# MXChip-EMW3166-v1_0_0.net
KiCad netlist of a schematic drawn in EAGLE
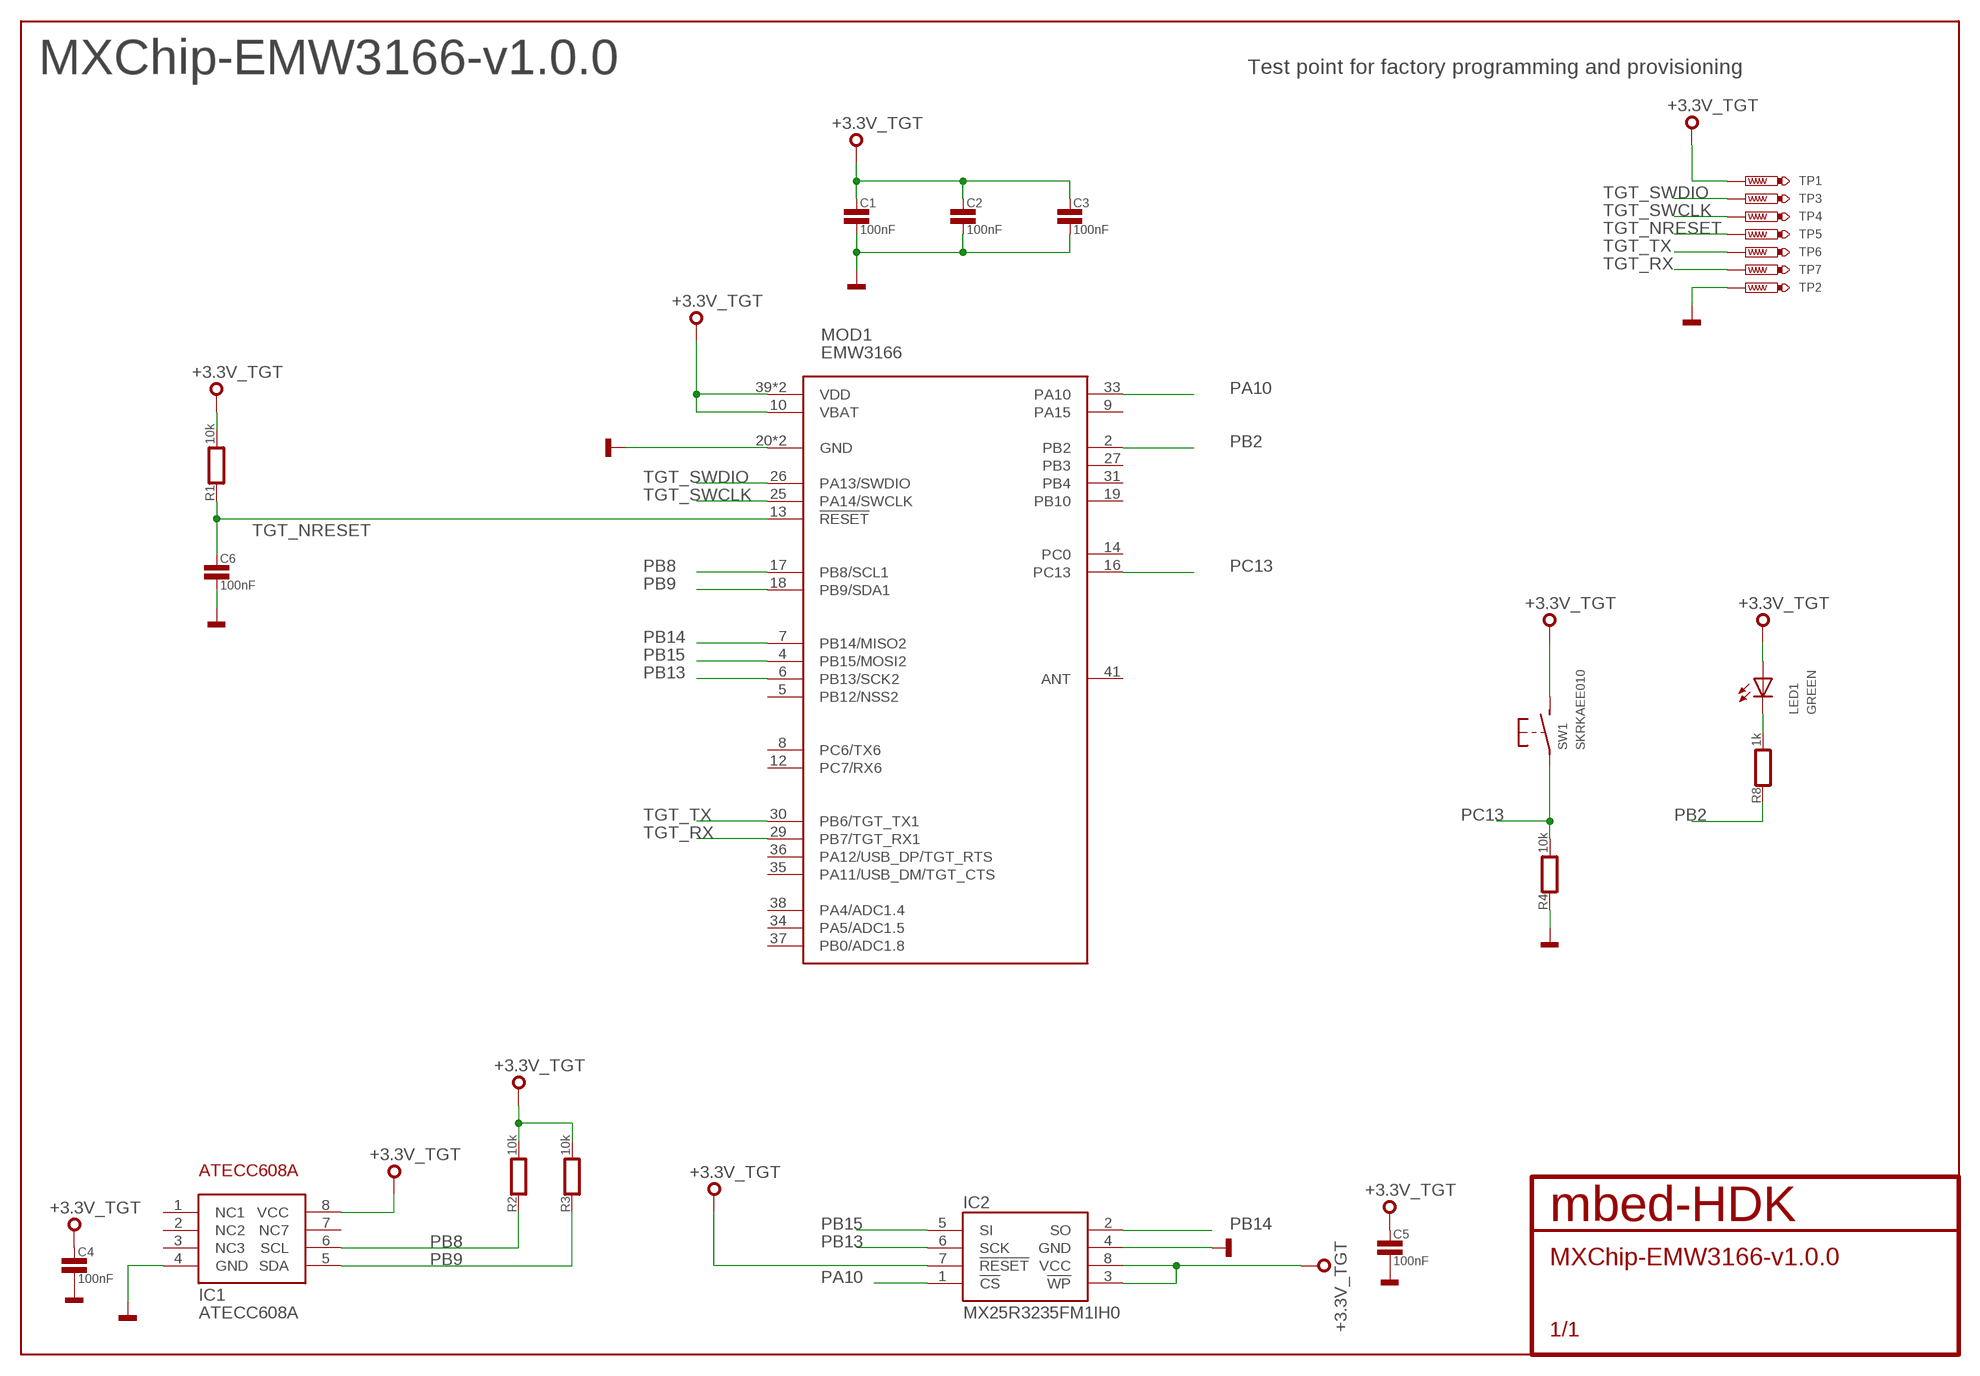
[diagram p0: schematic, sheet 1]

(export (version "E")
  (design (tool "Eeschema 10.0.6"))
  (components
    (comp (ref "C1")
      (value "100nF")
      (footprint "eagle-import:0603")
      (libsource (lib "eagle-import") (part "C0603"))
    )
    (comp (ref "C2")
      (value "100nF")
      (footprint "eagle-import:0603")
      (libsource (lib "eagle-import") (part "C0603"))
    )
    (comp (ref "C3")
      (value "100nF")
      (footprint "eagle-import:0603")
      (libsource (lib "eagle-import") (part "C0603"))
    )
    (comp (ref "C4")
      (value "100nF")
      (footprint "eagle-import:0603")
      (libsource (lib "eagle-import") (part "C0603"))
    )
    (comp (ref "C5")
      (value "100nF")
      (footprint "eagle-import:0603")
      (libsource (lib "eagle-import") (part "C0603"))
    )
    (comp (ref "C6")
      (value "100nF")
      (footprint "eagle-import:0603")
      (libsource (lib "eagle-import") (part "C0603"))
    )
    (comp (ref "IC1")
      (value "ATECC608A")
      (footprint "eagle-import:SO8")
      (fields (field (name "MF") "Atmel"))
      (libsource (lib "eagle-import") (part "ATECC608A"))
    )
    (comp (ref "IC2")
      (value "MX25R3235FM1IH0")
      (footprint "eagle-import:SO8")
      (fields (field (name "MF") "Macronix"))
      (libsource (lib "eagle-import") (part "MX25R3235FM1IH0"))
    )
    (comp (ref "LED1")
      (value "GREEN")
      (footprint "eagle-import:CHIPLED_0603")
      (fields (field (name "MF") "Wurth Electronics Inc"))
      (libsource (lib "eagle-import") (part "SMD_LED0603"))
    )
    (comp (ref "MOD1")
      (value "EMW3166")
      (footprint "eagle-import:EMW3166")
      (libsource (lib "eagle-import") (part "EMW3166"))
    )
    (comp (ref "R1")
      (value "10k")
      (footprint "eagle-import:0603")
      (libsource (lib "eagle-import") (part "R0603"))
    )
    (comp (ref "R2")
      (value "10k")
      (footprint "eagle-import:0603")
      (libsource (lib "eagle-import") (part "R0603"))
    )
    (comp (ref "R3")
      (value "10k")
      (footprint "eagle-import:0603")
      (libsource (lib "eagle-import") (part "R0603"))
    )
    (comp (ref "R4")
      (value "10k")
      (footprint "eagle-import:0603")
      (libsource (lib "eagle-import") (part "R0603"))
    )
    (comp (ref "R8")
      (value "1k")
      (footprint "eagle-import:0603")
      (libsource (lib "eagle-import") (part "R0603"))
    )
    (comp (ref "SW1")
      (value "SKRKAEE010")
      (footprint "eagle-import:SKRKAEE010")
      (fields (field (name "MF") "ALPS"))
      (libsource (lib "eagle-import") (part "SKRKAEE010"))
    )
    (comp (ref "TP1")
      (value "TEST_POINT-50R-SMD")
      (footprint "eagle-import:TP50-SMD")
      (libsource (lib "eagle-import") (part "TEST_POINT-50R-SMD"))
    )
    (comp (ref "TP2")
      (value "TEST_POINT-50R-SMD")
      (footprint "eagle-import:TP50-SMD")
      (libsource (lib "eagle-import") (part "TEST_POINT-50R-SMD"))
    )
    (comp (ref "TP3")
      (value "TEST_POINT-50R-SMD")
      (footprint "eagle-import:TP50-SMD")
      (libsource (lib "eagle-import") (part "TEST_POINT-50R-SMD"))
    )
    (comp (ref "TP4")
      (value "TEST_POINT-50R-SMD")
      (footprint "eagle-import:TP50-SMD")
      (libsource (lib "eagle-import") (part "TEST_POINT-50R-SMD"))
    )
    (comp (ref "TP5")
      (value "TEST_POINT-50R-SMD")
      (footprint "eagle-import:TP50-SMD")
      (libsource (lib "eagle-import") (part "TEST_POINT-50R-SMD"))
    )
    (comp (ref "TP6")
      (value "TEST_POINT-50R-SMD")
      (footprint "eagle-import:TP50-SMD")
      (libsource (lib "eagle-import") (part "TEST_POINT-50R-SMD"))
    )
    (comp (ref "TP7")
      (value "TEST_POINT-50R-SMD")
      (footprint "eagle-import:TP50-SMD")
      (libsource (lib "eagle-import") (part "TEST_POINT-50R-SMD"))
    )
  )
  (nets
    (net (code "1") (name "+3.3V_TGT") (class "Default")
      (node (ref "C1") (pin "1") (pinfunction "P$1_1") (pintype "passive"))
      (node (ref "C2") (pin "1") (pinfunction "P$1_1") (pintype "passive"))
      (node (ref "C3") (pin "1") (pinfunction "P$1_1") (pintype "passive"))
      (node (ref "C4") (pin "1") (pinfunction "P$1_1") (pintype "passive"))
      (node (ref "C5") (pin "1") (pinfunction "P$1_1") (pintype "passive"))
      (node (ref "IC1") (pin "8") (pinfunction "VCC_8") (pintype "bidirectional"))
      (node (ref "IC2") (pin "3") (pinfunction "~{WP}_3") (pintype "bidirectional"))
      (node (ref "IC2") (pin "7") (pinfunction "~{RESET}_7") (pintype "bidirectional"))
      (node (ref "IC2") (pin "8") (pinfunction "VCC_8") (pintype "bidirectional"))
      (node (ref "LED1") (pin "A") (pinfunction "A_A") (pintype "passive"))
      (node (ref "MOD1") (pin "10") (pinfunction "VBAT_10") (pintype "bidirectional"))
      (node (ref "MOD1") (pin "39") (pinfunction "VDD_39") (pintype "bidirectional"))
      (node (ref "MOD1") (pin "40") (pinfunction "VDD_40") (pintype "bidirectional"))
      (node (ref "R1") (pin "2") (pinfunction "P$2_2") (pintype "passive"))
      (node (ref "R2") (pin "2") (pinfunction "P$2_2") (pintype "passive"))
      (node (ref "R3") (pin "2") (pinfunction "P$2_2") (pintype "passive"))
      (node (ref "SW1") (pin "P$2") (pinfunction "S_P$2") (pintype "passive"))
      (node (ref "TP1") (pin "TP") (pinfunction "TP_TP") (pintype "input"))
    )
    (net (code "2") (name "/PA10") (class "Default")
      (node (ref "IC2") (pin "1") (pinfunction "~{CS}_1") (pintype "bidirectional"))
      (node (ref "MOD1") (pin "33") (pinfunction "PA10_33") (pintype "bidirectional"))
    )
    (net (code "3") (name "/PB2") (class "Default")
      (node (ref "MOD1") (pin "2") (pinfunction "PB2_2") (pintype "bidirectional"))
      (node (ref "R8") (pin "1") (pinfunction "P$1_1") (pintype "passive"))
    )
    (net (code "4") (name "/PB8") (class "Default")
      (node (ref "IC1") (pin "6") (pinfunction "SCL_6") (pintype "bidirectional"))
      (node (ref "MOD1") (pin "17") (pinfunction "PB8/SCL1_17") (pintype "bidirectional"))
      (node (ref "R2") (pin "1") (pinfunction "P$1_1") (pintype "passive"))
    )
    (net (code "5") (name "/PB9") (class "Default")
      (node (ref "IC1") (pin "5") (pinfunction "SDA_5") (pintype "bidirectional"))
      (node (ref "MOD1") (pin "18") (pinfunction "PB9/SDA1_18") (pintype "bidirectional"))
      (node (ref "R3") (pin "1") (pinfunction "P$1_1") (pintype "passive"))
    )
    (net (code "6") (name "/PB13") (class "Default")
      (node (ref "IC2") (pin "6") (pinfunction "SCK_6") (pintype "bidirectional"))
      (node (ref "MOD1") (pin "6") (pinfunction "PB13/SCK2_6") (pintype "bidirectional"))
    )
    (net (code "7") (name "/PB14") (class "Default")
      (node (ref "IC2") (pin "2") (pinfunction "SO_2") (pintype "bidirectional"))
      (node (ref "MOD1") (pin "7") (pinfunction "PB14/MISO2_7") (pintype "bidirectional"))
    )
    (net (code "8") (name "/PB15") (class "Default")
      (node (ref "IC2") (pin "5") (pinfunction "SI_5") (pintype "bidirectional"))
      (node (ref "MOD1") (pin "4") (pinfunction "PB15/MOSI2_4") (pintype "bidirectional"))
    )
    (net (code "9") (name "/PC13") (class "Default")
      (node (ref "MOD1") (pin "16") (pinfunction "PC13_16") (pintype "bidirectional"))
      (node (ref "R4") (pin "2") (pinfunction "P$2_2") (pintype "passive"))
      (node (ref "SW1") (pin "P$1") (pinfunction "P_P$1") (pintype "passive"))
    )
    (net (code "10") (name "/TGT_NRESET") (class "Default")
      (node (ref "C6") (pin "1") (pinfunction "P$1_1") (pintype "passive"))
      (node (ref "MOD1") (pin "13") (pinfunction "~{RESET}_13") (pintype "bidirectional"))
      (node (ref "R1") (pin "1") (pinfunction "P$1_1") (pintype "passive"))
      (node (ref "TP5") (pin "TP") (pinfunction "TP_TP") (pintype "input"))
    )
    (net (code "11") (name "/TGT_RX") (class "Default")
      (node (ref "MOD1") (pin "29") (pinfunction "PB7/TGT_RX1_29") (pintype "bidirectional"))
      (node (ref "TP7") (pin "TP") (pinfunction "TP_TP") (pintype "input"))
    )
    (net (code "12") (name "/TGT_SWCLK") (class "Default")
      (node (ref "MOD1") (pin "25") (pinfunction "PA14/SWCLK_25") (pintype "bidirectional"))
      (node (ref "TP4") (pin "TP") (pinfunction "TP_TP") (pintype "input"))
    )
    (net (code "13") (name "/TGT_SWDIO") (class "Default")
      (node (ref "MOD1") (pin "26") (pinfunction "PA13/SWDIO_26") (pintype "bidirectional"))
      (node (ref "TP3") (pin "TP") (pinfunction "TP_TP") (pintype "input"))
    )
    (net (code "14") (name "/TGT_TX") (class "Default")
      (node (ref "MOD1") (pin "30") (pinfunction "PB6/TGT_TX1_30") (pintype "bidirectional"))
      (node (ref "TP6") (pin "TP") (pinfunction "TP_TP") (pintype "input"))
    )
    (net (code "15") (name "GND") (class "Default")
      (node (ref "C1") (pin "2") (pinfunction "P$2_2") (pintype "passive"))
      (node (ref "C2") (pin "2") (pinfunction "P$2_2") (pintype "passive"))
      (node (ref "C3") (pin "2") (pinfunction "P$2_2") (pintype "passive"))
      (node (ref "C4") (pin "2") (pinfunction "P$2_2") (pintype "passive"))
      (node (ref "C5") (pin "2") (pinfunction "P$2_2") (pintype "passive"))
      (node (ref "C6") (pin "2") (pinfunction "P$2_2") (pintype "passive"))
      (node (ref "IC1") (pin "4") (pinfunction "GND_4") (pintype "bidirectional"))
      (node (ref "IC2") (pin "4") (pinfunction "GND_4") (pintype "bidirectional"))
      (node (ref "MOD1") (pin "20") (pinfunction "GND_20") (pintype "bidirectional"))
      (node (ref "MOD1") (pin "21") (pinfunction "GND_21") (pintype "bidirectional"))
      (node (ref "R4") (pin "1") (pinfunction "P$1_1") (pintype "passive"))
      (node (ref "TP2") (pin "TP") (pinfunction "TP_TP") (pintype "input"))
    )
    (net (code "16") (name "Net-(R8-P$2)") (class "Default")
      (node (ref "LED1") (pin "C") (pinfunction "C_C") (pintype "passive"))
      (node (ref "R8") (pin "2") (pinfunction "P$2_2") (pintype "passive"))
    )
    (net (code "17") (name "unconnected-(IC1-NC1-Pad1)") (class "Default")
      (node (ref "IC1") (pin "1") (pinfunction "NC1_1") (pintype "bidirectional"))
    )
    (net (code "18") (name "unconnected-(IC1-NC2-Pad2)") (class "Default")
      (node (ref "IC1") (pin "2") (pinfunction "NC2_2") (pintype "bidirectional"))
    )
    (net (code "19") (name "unconnected-(IC1-NC3-Pad3)") (class "Default")
      (node (ref "IC1") (pin "3") (pinfunction "NC3_3") (pintype "bidirectional"))
    )
    (net (code "20") (name "unconnected-(IC1-NC7-Pad7)") (class "Default")
      (node (ref "IC1") (pin "7") (pinfunction "NC7_7") (pintype "bidirectional"))
    )
    (net (code "21") (name "unconnected-(MOD1-ANT-Pad41)") (class "Default")
      (node (ref "MOD1") (pin "41") (pinfunction "ANT_41") (pintype "bidirectional"))
    )
    (net (code "22") (name "unconnected-(MOD1-PA4{slash}ADC1.4-Pad38)") (class "Default")
      (node (ref "MOD1") (pin "38") (pinfunction "PA4/ADC1.4_38") (pintype "bidirectional"))
    )
    (net (code "23") (name "unconnected-(MOD1-PA5{slash}ADC1.5-Pad34)") (class "Default")
      (node (ref "MOD1") (pin "34") (pinfunction "PA5/ADC1.5_34") (pintype "bidirectional"))
    )
    (net (code "24") (name "unconnected-(MOD1-PA11{slash}USB_DM{slash}TGT_CTS-Pad35)") (class "Default")
      (node (ref "MOD1") (pin "35") (pinfunction "PA11/USB_DM/TGT_CTS_35") (pintype "bidirectional"))
    )
    (net (code "25") (name "unconnected-(MOD1-PA12{slash}USB_DP{slash}TGT_RTS-Pad36)") (class "Default")
      (node (ref "MOD1") (pin "36") (pinfunction "PA12/USB_DP/TGT_RTS_36") (pintype "bidirectional"))
    )
    (net (code "26") (name "unconnected-(MOD1-PA15-Pad9)") (class "Default")
      (node (ref "MOD1") (pin "9") (pinfunction "PA15_9") (pintype "bidirectional"))
    )
    (net (code "27") (name "unconnected-(MOD1-PB0{slash}ADC1.8-Pad37)") (class "Default")
      (node (ref "MOD1") (pin "37") (pinfunction "PB0/ADC1.8_37") (pintype "bidirectional"))
    )
    (net (code "28") (name "unconnected-(MOD1-PB3-Pad27)") (class "Default")
      (node (ref "MOD1") (pin "27") (pinfunction "PB3_27") (pintype "bidirectional"))
    )
    (net (code "29") (name "unconnected-(MOD1-PB4-Pad31)") (class "Default")
      (node (ref "MOD1") (pin "31") (pinfunction "PB4_31") (pintype "bidirectional"))
    )
    (net (code "30") (name "unconnected-(MOD1-PB10-Pad19)") (class "Default")
      (node (ref "MOD1") (pin "19") (pinfunction "PB10_19") (pintype "bidirectional"))
    )
    (net (code "31") (name "unconnected-(MOD1-PB12{slash}NSS2-Pad5)") (class "Default")
      (node (ref "MOD1") (pin "5") (pinfunction "PB12/NSS2_5") (pintype "bidirectional"))
    )
    (net (code "32") (name "unconnected-(MOD1-PC0-Pad14)") (class "Default")
      (node (ref "MOD1") (pin "14") (pinfunction "PC0_14") (pintype "bidirectional"))
    )
    (net (code "33") (name "unconnected-(MOD1-PC6{slash}TX6-Pad8)") (class "Default")
      (node (ref "MOD1") (pin "8") (pinfunction "PC6/TX6_8") (pintype "bidirectional"))
    )
    (net (code "34") (name "unconnected-(MOD1-PC7{slash}RX6-Pad12)") (class "Default")
      (node (ref "MOD1") (pin "12") (pinfunction "PC7/RX6_12") (pintype "bidirectional"))
    )
  )
)
